# STM32F103C8T6_Schematic.net
KiCad netlist of a schematic drawn in Altium Designer
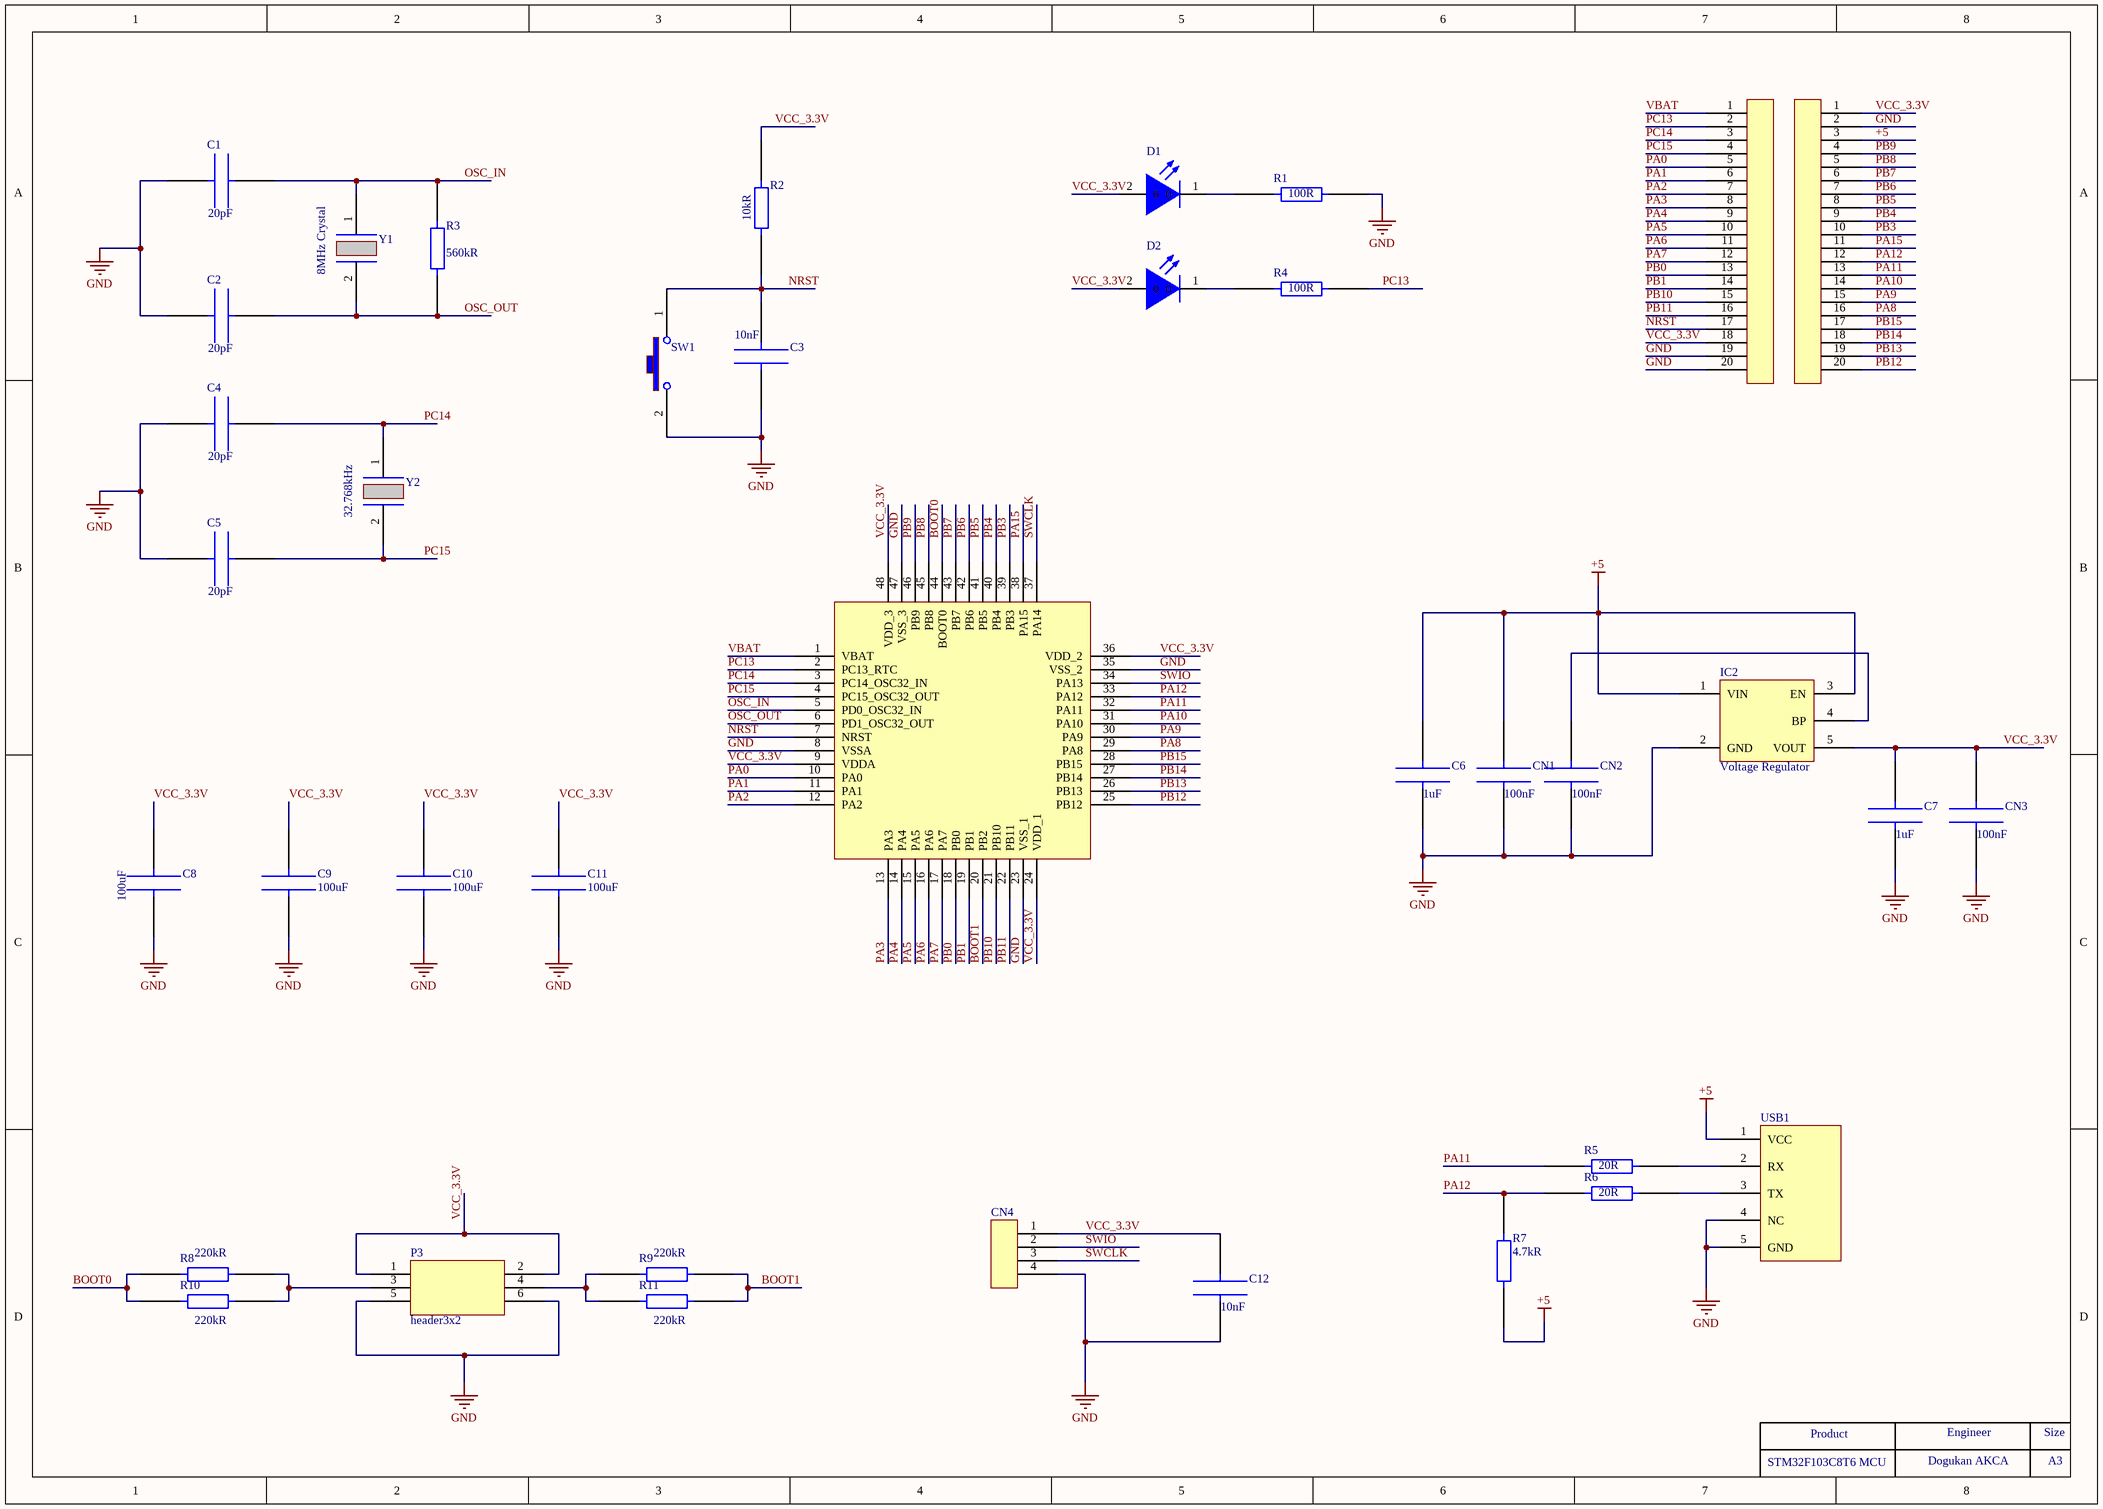
[diagram p0: STM32F103C8T6_Schematic.SchDoc]

(export (version "E")
  (design (tool "Eeschema 10.0.6"))
  (components
    (comp (ref "C1")
      (value "CAP CER 20PF 50V C0G/NP0 0603")
      (footprint "0603_CAP")
      (fields
        (field (name "MANUFACTURER") "Samsung")
        (field (name "MANUFACTURER PART NUMBER") "CL10C200JB8NNNC")
        (field (name "TOLERANCE") "5%")
        (field (name "CAPACITANCE") "20pF")
        (field (name "DESIGNER") "Dogukan")
      )
      (libsource (lib "STM32F103C8T6_Library") (part "CAP CER 20PF 50V C0G/NP0 0603"))
    )
    (comp (ref "C2")
      (value "CAP CER 20PF 50V C0G/NP0 0603")
      (footprint "0603_CAP")
      (fields
        (field (name "MANUFACTURER") "Samsung")
        (field (name "MANUFACTURER PART NUMBER") "CL10C200JB8NNNC")
        (field (name "TOLERANCE") "5%")
        (field (name "CAPACITANCE") "20pF")
        (field (name "DESIGNER") "Dogukan")
      )
      (libsource (lib "STM32F103C8T6_Library") (part "CAP CER 20PF 50V C0G/NP0 0603"))
    )
    (comp (ref "C3")
      (value "CAP CER 10nF 50V X7R 0603")
      (footprint "0603_CAP")
      (description "Cap Ceramic 0.01uF 50V X7R 5% SMD 0603 125C Paper T/R")
      (fields
        (field (name "MANUFACTURER") "Yageo")
        (field (name "MANUFACTURER PART NUMBER") "CC0603JPX7R9BB103")
        (field (name "CAPACITANCE") "10nF")
        (field (name "DESIGNER") "Dogukan")
      )
      (libsource (lib "STM32F103C8T6_Library") (part "CAP CER 10nF 50V X7R 0603"))
    )
    (comp (ref "C4")
      (value "CAP CER 20PF 50V C0G/NP0 0603")
      (footprint "0603_CAP")
      (fields
        (field (name "MANUFACTURER") "Samsung")
        (field (name "MANUFACTURER PART NUMBER") "CL10C200JB8NNNC")
        (field (name "TOLERANCE") "5%")
        (field (name "CAPACITANCE") "20pF")
        (field (name "DESIGNER") "Dogukan")
      )
      (libsource (lib "STM32F103C8T6_Library") (part "CAP CER 20PF 50V C0G/NP0 0603"))
    )
    (comp (ref "C5")
      (value "CAP CER 20PF 50V C0G/NP0 0603")
      (footprint "0603_CAP")
      (fields
        (field (name "MANUFACTURER") "Samsung")
        (field (name "MANUFACTURER PART NUMBER") "CL10C200JB8NNNC")
        (field (name "TOLERANCE") "5%")
        (field (name "CAPACITANCE") "20pF")
        (field (name "DESIGNER") "Dogukan")
      )
      (libsource (lib "STM32F103C8T6_Library") (part "CAP CER 20PF 50V C0G/NP0 0603"))
    )
    (comp (ref "C6")
      (value "CAP CER 1UF 0805")
      (footprint "CAP_0805")
      (description "CAP CER 1UF 50V X7R 0805")
      (fields
        (field (name "MANUFACTURER") "Samsung")
        (field (name "MANUFACTURER PART NUMBER") "CL21B105KBFNNNE")
        (field (name "CAPACITANCE") "1uF")
        (field (name "DESIGNER") "Dogukan")
      )
      (libsource (lib "STM32F103C8T6_Library") (part "CAP CER 1UF 0805"))
    )
    (comp (ref "C7")
      (value "CAP CER 1UF 0805")
      (footprint "CAP_0805")
      (description "CAP CER 1UF 50V X7R 0805")
      (fields
        (field (name "MANUFACTURER") "Samsung")
        (field (name "MANUFACTURER PART NUMBER") "CL21B105KBFNNNE")
        (field (name "CAPACITANCE") "1uF")
        (field (name "DESIGNER") "Dogukan")
      )
      (libsource (lib "STM32F103C8T6_Library") (part "CAP CER 1UF 0805"))
    )
    (comp (ref "C8")
      (value "CAP CER 100uf MLCC")
      (footprint "CAP_0805")
      (description "Cap 100UF 4VDC Z6S 20% SMD 0805 Embossed Tape")
      (fields
        (field (name "MANUFACTURER") "Murata")
        (field (name "MANUFACTURER PART NUMBER") "GRM21BC80G107ME15K")
        (field (name "CAPACITANCE") "100uF")
        (field (name "DESIGNER") "Dogukan")
      )
      (libsource (lib "STM32F103C8T6_Library") (part "CAP CER 100uf MLCC"))
    )
    (comp (ref "C9")
      (value "CAP CER 100uf MLCC")
      (footprint "CAP_0805")
      (description "Cap 100UF 4VDC Z6S 20% SMD 0805 Embossed Tape")
      (fields
        (field (name "MANUFACTURER") "Murata")
        (field (name "MANUFACTURER PART NUMBER") "GRM21BC80G107ME15K")
        (field (name "CAPACITANCE") "100uF")
        (field (name "DESIGNER") "Dogukan")
      )
      (libsource (lib "STM32F103C8T6_Library") (part "CAP CER 100uf MLCC"))
    )
    (comp (ref "C10")
      (value "CAP CER 100uf MLCC")
      (footprint "CAP_0805")
      (description "Cap 100UF 4VDC Z6S 20% SMD 0805 Embossed Tape")
      (fields
        (field (name "MANUFACTURER") "Murata")
        (field (name "MANUFACTURER PART NUMBER") "GRM21BC80G107ME15K")
        (field (name "CAPACITANCE") "100uF")
        (field (name "DESIGNER") "Dogukan")
      )
      (libsource (lib "STM32F103C8T6_Library") (part "CAP CER 100uf MLCC"))
    )
    (comp (ref "C11")
      (value "CAP CER 100uf MLCC")
      (footprint "CAP_0805")
      (description "Cap 100UF 4VDC Z6S 20% SMD 0805 Embossed Tape")
      (fields
        (field (name "MANUFACTURER") "Murata")
        (field (name "MANUFACTURER PART NUMBER") "GRM21BC80G107ME15K")
        (field (name "CAPACITANCE") "100uF")
        (field (name "DESIGNER") "Dogukan")
      )
      (libsource (lib "STM32F103C8T6_Library") (part "CAP CER 100uf MLCC"))
    )
    (comp (ref "C12")
      (value "CAP CER 10nF 50V X7R 0603")
      (footprint "0603_CAP")
      (description "Cap Ceramic 0.01uF 50V X7R 5% SMD 0603 125C Paper T/R")
      (fields
        (field (name "MANUFACTURER") "Yageo")
        (field (name "MANUFACTURER PART NUMBER") "CC0603JPX7R9BB103")
        (field (name "CAPACITANCE") "10nF")
        (field (name "DESIGNER") "Dogukan")
      )
      (libsource (lib "STM32F103C8T6_Library") (part "CAP CER 10nF 50V X7R 0603"))
    )
    (comp (ref "CN1")
      (value "C0603 0.1uf")
      (footprint "0603_CAP")
      (description "Multilayer Ceramic Capacitors (MLCC) - SMD/SMT 50volts 0.1uF X7R 10%")
      (fields
        (field (name "MANUFACTURER") "KEMET")
        (field (name "MANUFACTURER PART NUMBER") "C0603C104K5RACTU")
        (field (name "CAPACITANCE") "100nF")
        (field (name "DESIGNER") "Dogukan")
      )
      (libsource (lib "STM32F103C8T6_Library") (part "C0603 0.1uf"))
    )
    (comp (ref "CN2")
      (value "C0603 0.1uf")
      (footprint "0603_CAP")
      (description "Multilayer Ceramic Capacitors (MLCC) - SMD/SMT 50volts 0.1uF X7R 10%")
      (fields
        (field (name "MANUFACTURER") "KEMET")
        (field (name "MANUFACTURER PART NUMBER") "C0603C104K5RACTU")
        (field (name "CAPACITANCE") "100nF")
        (field (name "DESIGNER") "Dogukan")
      )
      (libsource (lib "STM32F103C8T6_Library") (part "C0603 0.1uf"))
    )
    (comp (ref "CN3")
      (value "C0603 0.1uf")
      (footprint "0603_CAP")
      (description "Multilayer Ceramic Capacitors (MLCC) - SMD/SMT 50volts 0.1uF X7R 10%")
      (fields
        (field (name "MANUFACTURER") "KEMET")
        (field (name "MANUFACTURER PART NUMBER") "C0603C104K5RACTU")
        (field (name "CAPACITANCE") "100nF")
        (field (name "DESIGNER") "Dogukan")
      )
      (libsource (lib "STM32F103C8T6_Library") (part "C0603 0.1uf"))
    )
    (comp (ref "CN4")
      (value "CONN HDR STRIP SOLDER 4POS GOLD")
      (footprint "4 pin konnektor pin")
      (description "Headers & Wire Housings Low Profile RT Angle Solder Cup Header")
      (fields
        (field (name "MANUFACTURER") "Mill-Max")
        (field (name "MANUFACTURER PART NUMBER") "380-10-104-10-003000")
        (field (name "DESIGNER") "Dogukan")
      )
      (libsource (lib "STM32F103C8T6_Library") (part "KONNEKTOR 4POS"))
    )
    (comp (ref "D1")
      (value "LED GREEN CLEAR CHIP SMD")
      (footprint "0805_LED_GREEN")
      (description "Green 569nm LED Indication - Discrete 2.1V 0805 (2012 Metric)")
      (fields
        (field (name "MANUFACTURER") "Vishay Lite-On")
        (field (name "MANUFACTURER PART NUMBER") "LTST-C171GKT")
        (field (name "DESIGNER") "Dogukan")
      )
      (libsource (lib "STM32F103C8T6_Library") (part "LED GREEN CLEAR CHIP SMD"))
    )
    (comp (ref "D2")
      (value "LED GREEN CLEAR CHIP SMD")
      (footprint "0805_LED_GREEN")
      (description "Green 569nm LED Indication - Discrete 2.1V 0805 (2012 Metric)")
      (fields
        (field (name "MANUFACTURER") "Vishay Lite-On")
        (field (name "MANUFACTURER PART NUMBER") "LTST-C171GKT")
        (field (name "DESIGNER") "Dogukan")
      )
      (libsource (lib "STM32F103C8T6_Library") (part "LED GREEN CLEAR CHIP SMD"))
    )
    (comp (ref "IC1")
      (value "IC MCU 32BIT 64KB FLASH 48LQFP")
      (footprint "LQFP48")
      (description "ARM Cortex-M3 STM32 F1 Microcontroller 32-Bit 72MHz 64kB FLASH LQFP48 STM32F103C8T6")
      (fields
        (field (name "MANUFACTURER") "STMicroelectronics")
        (field (name "MANUFACTURER PART NUMBER") "STM32F103C8T6")
        (field (name "DESIGNER") "Dogukan")
      )
      (libsource (lib "STM32F103C8T6_Library") (part "STM32F103C8T6"))
    )
    (comp (ref "IC2")
      (value "IC REG LINEAR 3.3V 300MA SOT23-5")
      (footprint "SOT23-5")
      (description "IC REG LDO 3.3V 0.3A SOT23-5")
      (fields
        (field (name "MANUFACTURER") "Richtek")
        (field (name "MANUFACTURER PART NUMBER") "RT9193-33GB")
        (field (name "CATEGORY") "Voltage Regulator")
        (field (name "DESIGNER") "Dogukan")
      )
      (libsource (lib "STM32F103C8T6_Library") (part "Voltage Regulator_5V-{gt}3.3V"))
    )
    (comp (ref "P1")
      (value "CONN SIL HDR MALE PIN 20POS TIN")
      (footprint "20pin1x20_header_connector")
      (description "2.54mm (0.1\") Pitch SIL Vertical Through Connect Header Strip, tin (hi-temp mould), 20 contacts")
      (fields
        (field (name "MANUFACTURER") "Harwin")
        (field (name "MANUFACTURER PART NUMBER") "D01-9922046")
        (field (name "DESIGNER") "Dogukan")
      )
      (libsource (lib "") (part "header_20pin_1"))
    )
    (comp (ref "P2")
      (value "CONN SIL HDR MALE PIN 20POS TIN")
      (footprint "20pin1x20_header_connector")
      (description "2.54mm (0.1\") Pitch SIL Vertical Through Connect Header Strip, tin (hi-temp mould), 20 contacts")
      (fields
        (field (name "MANUFACTURER") "Harwin")
        (field (name "MANUFACTURER PART NUMBER") "D01-9922046")
        (field (name "DESIGNER") "Dogukan")
      )
      (libsource (lib "STM32F103C8T6_Library") (part "header_20pin"))
    )
    (comp (ref "P3")
      (value "header3x2")
      (footprint "header3x2")
      (fields (field (name "DESIGNER") "Dogukan"))
      (libsource (lib "STM32F103C8T6_Library") (part "header3x2"))
    )
    (comp (ref "R1")
      (value "100R")
      (footprint "0603_RES")
      (description "Res Thick Film 0603 100 Ohm 1% 1/10W ±100ppm/°C Molded SMD Paper T/R")
      (fields
        (field (name "MANUFACTURER") "Yageo")
        (field (name "MANUFACTURER PART NUMBER") "RC0603FR-07100RL")
        (field (name "DESIGNER") "Dogukan")
      )
      (libsource (lib "STM32F103C8T6_Library") (part "RES_100R_0603"))
    )
    (comp (ref "R2")
      (value "RES 10K OHM 0.5% 1/10W 0603")
      (footprint "0603_RES")
      (description "Res Thin Film 0603 10K Ohm 0.5% 1/10W ±25ppm/°C Molded SMD Paper T/R")
      (fields
        (field (name "MANUFACTURER") "Yageo")
        (field (name "MANUFACTURER PART NUMBER") "RT0603DRD0710KL")
        (field (name "RESISTANCE") "10kR")
        (field (name "DESIGNER") "Dogukan")
      )
      (libsource (lib "STM32F103C8T6_Library") (part "RES 10K OHM 0.5% 1/10W 0603"))
    )
    (comp (ref "R3")
      (value "RES 560K OHM 5% 1/10W 0603")
      (footprint "0603_RES")
      (description "Res Thick Film 0603 560K Ohm 5% 0.1W(1/10W) ±100ppm/C Molded SMD Paper T/R")
      (fields
        (field (name "MANUFACTURER") "Yageo")
        (field (name "MANUFACTURER PART NUMBER") "RC0603JR-07560KL")
        (field (name "RESISTANCE") "560kR")
        (field (name "DESIGNER") "Dogukan")
      )
      (libsource (lib "STM32F103C8T6_Library") (part "RES 560K OHM 5% 1/10W 0603"))
    )
    (comp (ref "R4")
      (value "100R")
      (footprint "0603_RES")
      (description "Res Thick Film 0603 100 Ohm 1% 1/10W ±100ppm/°C Molded SMD Paper T/R")
      (fields
        (field (name "MANUFACTURER") "Yageo")
        (field (name "MANUFACTURER PART NUMBER") "RC0603FR-07100RL")
        (field (name "DESIGNER") "Dogukan")
      )
      (libsource (lib "STM32F103C8T6_Library") (part "RES_100R_0603"))
    )
    (comp (ref "R5")
      (value "*RES 20 OHM 5% 1/10W 0603")
      (footprint "0603_RES")
      (description "Res Thick Film 0603 20 Ohm 5% 1/10W +/-100ppm/ßC Molded SMD Paper T/R")
      (fields
        (field (name "MANUFACTURER") "Yageo")
        (field (name "MANUFACTURER PART NUMBER") "RC0603JR-0720RL")
        (field (name "R") "20R")
        (field (name "DESIGNER") "Dogukan")
      )
      (libsource (lib "STM32F103C8T6_Library") (part "RES 20 OHM 5% 1/10W 0603"))
    )
    (comp (ref "R6")
      (value "*RES 20 OHM 5% 1/10W 0603")
      (footprint "0603_RES")
      (description "Res Thick Film 0603 20 Ohm 5% 1/10W +/-100ppm/ßC Molded SMD Paper T/R")
      (fields
        (field (name "MANUFACTURER") "Yageo")
        (field (name "MANUFACTURER PART NUMBER") "RC0603JR-0720RL")
        (field (name "R") "20R")
        (field (name "DESIGNER") "Dogukan")
      )
      (libsource (lib "STM32F103C8T6_Library") (part "RES 20 OHM 5% 1/10W 0603"))
    )
    (comp (ref "R7")
      (value "RES 4.7K OHM 5% 1/10W 0603")
      (footprint "0603_RES")
      (description "Res General Purpose Thick Film 0603 4.7k Ohm 5% 1/10W ±100ppm/°C Molded Paper T/R")
      (fields
        (field (name "MANUFACTURER") "Yageo")
        (field (name "MANUFACTURER PART NUMBER") "RC0603JR-074K7L")
        (field (name "RESISTANCE") "4.7kR")
        (field (name "DESIGNER") "Dogukan")
      )
      (libsource (lib "STM32F103C8T6_Library") (part "RES 4.7K OHM 5% 1/10W 0603"))
    )
    (comp (ref "R8")
      (value "RES 220K OHM 5% 1/10W 0603")
      (footprint "0603_RES")
      (description "Res Thick Film 0603 220K Ohm 5% 0.1W(1/10W) ±100ppm/C Pad SMD T/R")
      (fields
        (field (name "MANUFACTURER") "Yageo")
        (field (name "MANUFACTURER PART NUMBER") "RC0603JR-07220KL")
        (field (name "RESISTANCE") "220kR")
        (field (name "DESIGNER") "Dogukan")
      )
      (libsource (lib "STM32F103C8T6_Library") (part "RES 220K OHM 5% 1/10W 0603"))
    )
    (comp (ref "R9")
      (value "RES 220K OHM 5% 1/10W 0603")
      (footprint "0603_RES")
      (description "Res Thick Film 0603 220K Ohm 5% 0.1W(1/10W) ±100ppm/C Pad SMD T/R")
      (fields
        (field (name "MANUFACTURER") "Yageo")
        (field (name "MANUFACTURER PART NUMBER") "RC0603JR-07220KL")
        (field (name "RESISTANCE") "220kR")
        (field (name "DESIGNER") "Dogukan")
      )
      (libsource (lib "STM32F103C8T6_Library") (part "RES 220K OHM 5% 1/10W 0603"))
    )
    (comp (ref "R10")
      (value "RES 220K OHM 5% 1/10W 0603")
      (footprint "0603_RES")
      (description "Res Thick Film 0603 220K Ohm 5% 0.1W(1/10W) ±100ppm/C Pad SMD T/R")
      (fields
        (field (name "MANUFACTURER") "Yageo")
        (field (name "MANUFACTURER PART NUMBER") "RC0603JR-07220KL")
        (field (name "RESISTANCE") "220kR")
        (field (name "DESIGNER") "Dogukan")
      )
      (libsource (lib "STM32F103C8T6_Library") (part "RES 220K OHM 5% 1/10W 0603"))
    )
    (comp (ref "R11")
      (value "RES 220K OHM 5% 1/10W 0603")
      (footprint "0603_RES")
      (description "Res Thick Film 0603 220K Ohm 5% 0.1W(1/10W) ±100ppm/C Pad SMD T/R")
      (fields
        (field (name "MANUFACTURER") "Yageo")
        (field (name "MANUFACTURER PART NUMBER") "RC0603JR-07220KL")
        (field (name "RESISTANCE") "220kR")
        (field (name "DESIGNER") "Dogukan")
      )
      (libsource (lib "STM32F103C8T6_Library") (part "RES 220K OHM 5% 1/10W 0603"))
    )
    (comp (ref "SW1")
      (value "push button switch")
      (footprint "push_button")
      (libsource (lib "STM32F103C8T6_Library") (part "push_button"))
    )
    (comp (ref "USB1")
      (value "CONN RCPT USB2.0 MICRO B SMD R/A")
      (footprint "MICRO B USB2.0 SMD R/A")
      (description "CONN USB MICRO B RECPT SMT R/A")
      (fields
        (field (name "MANUFACTURER") "Amphenol ICC / FCI")
        (field (name "MANUFACTURER PART NUMBER") "10118192-0001LF")
        (field (name "DESIGNER") "Dogukan")
      )
      (libsource (lib "STM32F103C8T6_Library") (part "CONN RCPT USB2.0 MICRO B SMD R/A"))
    )
    (comp (ref "Y1")
      (value "CRYSTAL 8.0000MHZ 18PF SMD")
      (footprint "USX SMD T_8MHz Crystal")
      (description "Crystal 8MHz ±30ppm (Tol) ±50ppm (Stability) 18pF FUND 60Ohm 2-Pin HC-49/USX SMD T/R")
      (fields
        (field (name "MANUFACTURER") "ECS International")
        (field (name "MANUFACTURER PART NUMBER") "ECS-80-18-5PX-TR")
        (field (name "CATEGORY") "8MHz Crystal")
        (field (name "DESIGNER") "Dogukan")
      )
      (libsource (lib "STM32F103C8T6_Library") (part "CRYSTAL 8.0000MHZ 18PF SMD"))
    )
    (comp (ref "Y2")
      (value "CRYSTAL 32.7680KHZ 12.5PF SMD")
      (footprint "2-SMD_CRYSTAL 32.7680KHZ")
      (description "Crystal 0.032768MHz ±20ppm (Tol) 12.5pF Flexural 90000Ohm 2-Pin CSMD T/R")
      (fields
        (field (name "MANUFACTURER") "Abracon")
        (field (name "MANUFACTURER PART NUMBER") "ABS05-32.768KHZ-T")
        (field (name "FREQUENCY") "32.768kHz")
        (field (name "DESIGNER") "Dogukan")
      )
      (libsource (lib "STM32F103C8T6_Library") (part "CRYSTAL 32.7680KHZ 12.5PF SMD"))
    )
  )
  (nets
    (net (code "1") (name "+5") (class "Default")
      (node (ref "C6") (pin "2") (pinfunction "27_2") (pintype "passive"))
      (node (ref "CN1") (pin "2") (pinfunction "27_2") (pintype "passive"))
      (node (ref "IC2") (pin "1") (pinfunction "VIN_1") (pintype "passive"))
      (node (ref "IC2") (pin "3") (pinfunction "EN_3") (pintype "passive"))
      (node (ref "P2") (pin "3") (pinfunction "3_3") (pintype "passive"))
      (node (ref "R7") (pin "1") (pinfunction "25_1") (pintype "passive"))
      (node (ref "USB1") (pin "1") (pinfunction "VCC_1") (pintype "passive"))
    )
    (net (code "2") (name "/BOOT0") (class "Default")
      (node (ref "IC1") (pin "44") (pinfunction "BOOT0_44") (pintype "passive"))
      (node (ref "R10") (pin "1") (pinfunction "25_1") (pintype "passive"))
      (node (ref "R8") (pin "1") (pinfunction "25_1") (pintype "passive"))
    )
    (net (code "3") (name "/BOOT1") (class "Default")
      (node (ref "IC1") (pin "20") (pinfunction "PB2_20") (pintype "passive"))
      (node (ref "R11") (pin "2") (pinfunction "24_2") (pintype "passive"))
      (node (ref "R9") (pin "2") (pinfunction "24_2") (pintype "passive"))
    )
    (net (code "4") (name "/NRST") (class "Default")
      (node (ref "C3") (pin "2") (pinfunction "27_2") (pintype "passive"))
      (node (ref "IC1") (pin "7") (pinfunction "NRST_7") (pintype "passive"))
      (node (ref "P1") (pin "17") (pinfunction "17_17") (pintype "passive"))
      (node (ref "R2") (pin "1") (pinfunction "25_1") (pintype "passive"))
      (node (ref "SW1") (pin "1") (pinfunction "1_1") (pintype "passive"))
    )
    (net (code "5") (name "/OSC_IN") (class "Default")
      (node (ref "C1") (pin "2") (pinfunction "27_2") (pintype "passive"))
      (node (ref "IC1") (pin "5") (pinfunction "PD0_OSC32_IN_5") (pintype "passive"))
      (node (ref "R3") (pin "2") (pinfunction "24_2") (pintype "passive"))
      (node (ref "Y1") (pin "1") (pinfunction "4_1") (pintype "passive"))
    )
    (net (code "6") (name "/OSC_OUT") (class "Default")
      (node (ref "C2") (pin "2") (pinfunction "27_2") (pintype "passive"))
      (node (ref "IC1") (pin "6") (pinfunction "PD1_OSC32_OUT_6") (pintype "passive"))
      (node (ref "R3") (pin "1") (pinfunction "25_1") (pintype "passive"))
      (node (ref "Y1") (pin "2") (pinfunction "5_2") (pintype "passive"))
    )
    (net (code "7") (name "/PA0") (class "Default")
      (node (ref "IC1") (pin "10") (pinfunction "PA0_10") (pintype "passive"))
      (node (ref "P1") (pin "5") (pinfunction "5_5") (pintype "passive"))
    )
    (net (code "8") (name "/PA1") (class "Default")
      (node (ref "IC1") (pin "11") (pinfunction "PA1_11") (pintype "passive"))
      (node (ref "P1") (pin "6") (pinfunction "6_6") (pintype "passive"))
    )
    (net (code "9") (name "/PA2") (class "Default")
      (node (ref "IC1") (pin "12") (pinfunction "PA2_12") (pintype "passive"))
      (node (ref "P1") (pin "7") (pinfunction "7_7") (pintype "passive"))
    )
    (net (code "10") (name "/PA3") (class "Default")
      (node (ref "IC1") (pin "13") (pinfunction "PA3_13") (pintype "passive"))
      (node (ref "P1") (pin "8") (pinfunction "8_8") (pintype "passive"))
    )
    (net (code "11") (name "/PA4") (class "Default")
      (node (ref "IC1") (pin "14") (pinfunction "PA4_14") (pintype "passive"))
      (node (ref "P1") (pin "9") (pinfunction "9_9") (pintype "passive"))
    )
    (net (code "12") (name "/PA5") (class "Default")
      (node (ref "IC1") (pin "15") (pinfunction "PA5_15") (pintype "passive"))
      (node (ref "P1") (pin "10") (pinfunction "10_10") (pintype "passive"))
    )
    (net (code "13") (name "/PA6") (class "Default")
      (node (ref "IC1") (pin "16") (pinfunction "PA6_16") (pintype "passive"))
      (node (ref "P1") (pin "11") (pinfunction "11_11") (pintype "passive"))
    )
    (net (code "14") (name "/PA7") (class "Default")
      (node (ref "IC1") (pin "17") (pinfunction "PA7_17") (pintype "passive"))
      (node (ref "P1") (pin "12") (pinfunction "12_12") (pintype "passive"))
    )
    (net (code "15") (name "/PA8") (class "Default")
      (node (ref "IC1") (pin "29") (pinfunction "PA8_29") (pintype "passive"))
      (node (ref "P2") (pin "16") (pinfunction "16_16") (pintype "passive"))
    )
    (net (code "16") (name "/PA9") (class "Default")
      (node (ref "IC1") (pin "30") (pinfunction "PA9_30") (pintype "passive"))
      (node (ref "P2") (pin "15") (pinfunction "15_15") (pintype "passive"))
    )
    (net (code "17") (name "/PA10") (class "Default")
      (node (ref "IC1") (pin "31") (pinfunction "PA10_31") (pintype "passive"))
      (node (ref "P2") (pin "14") (pinfunction "14_14") (pintype "passive"))
    )
    (net (code "18") (name "/PA11") (class "Default")
      (node (ref "IC1") (pin "32") (pinfunction "PA11_32") (pintype "passive"))
      (node (ref "P2") (pin "13") (pinfunction "13_13") (pintype "passive"))
      (node (ref "R5") (pin "1") (pinfunction "25_1") (pintype "passive"))
    )
    (net (code "19") (name "/PA12") (class "Default")
      (node (ref "IC1") (pin "33") (pinfunction "PA12_33") (pintype "passive"))
      (node (ref "P2") (pin "12") (pinfunction "12_12") (pintype "passive"))
      (node (ref "R6") (pin "1") (pinfunction "25_1") (pintype "passive"))
      (node (ref "R7") (pin "2") (pinfunction "24_2") (pintype "passive"))
    )
    (net (code "20") (name "/PA15") (class "Default")
      (node (ref "IC1") (pin "38") (pinfunction "PA15_38") (pintype "passive"))
      (node (ref "P2") (pin "11") (pinfunction "11_11") (pintype "passive"))
    )
    (net (code "21") (name "/PB0") (class "Default")
      (node (ref "IC1") (pin "18") (pinfunction "PB0_18") (pintype "passive"))
      (node (ref "P1") (pin "13") (pinfunction "13_13") (pintype "passive"))
    )
    (net (code "22") (name "/PB1") (class "Default")
      (node (ref "IC1") (pin "19") (pinfunction "PB1_19") (pintype "passive"))
      (node (ref "P1") (pin "14") (pinfunction "14_14") (pintype "passive"))
    )
    (net (code "23") (name "/PB3") (class "Default")
      (node (ref "IC1") (pin "39") (pinfunction "PB3_39") (pintype "passive"))
      (node (ref "P2") (pin "10") (pinfunction "10_10") (pintype "passive"))
    )
    (net (code "24") (name "/PB4") (class "Default")
      (node (ref "IC1") (pin "40") (pinfunction "PB4_40") (pintype "passive"))
      (node (ref "P2") (pin "9") (pinfunction "9_9") (pintype "passive"))
    )
    (net (code "25") (name "/PB5") (class "Default")
      (node (ref "IC1") (pin "41") (pinfunction "PB5_41") (pintype "passive"))
      (node (ref "P2") (pin "8") (pinfunction "8_8") (pintype "passive"))
    )
    (net (code "26") (name "/PB6") (class "Default")
      (node (ref "IC1") (pin "42") (pinfunction "PB6_42") (pintype "passive"))
      (node (ref "P2") (pin "7") (pinfunction "7_7") (pintype "passive"))
    )
    (net (code "27") (name "/PB7") (class "Default")
      (node (ref "IC1") (pin "43") (pinfunction "PB7_43") (pintype "passive"))
      (node (ref "P2") (pin "6") (pinfunction "6_6") (pintype "passive"))
    )
    (net (code "28") (name "/PB8") (class "Default")
      (node (ref "IC1") (pin "45") (pinfunction "PB8_45") (pintype "passive"))
      (node (ref "P2") (pin "5") (pinfunction "5_5") (pintype "passive"))
    )
    (net (code "29") (name "/PB9") (class "Default")
      (node (ref "IC1") (pin "46") (pinfunction "PB9_46") (pintype "passive"))
      (node (ref "P2") (pin "4") (pinfunction "4_4") (pintype "passive"))
    )
    (net (code "30") (name "/PB10") (class "Default")
      (node (ref "IC1") (pin "21") (pinfunction "PB10_21") (pintype "passive"))
      (node (ref "P1") (pin "15") (pinfunction "15_15") (pintype "passive"))
    )
    (net (code "31") (name "/PB11") (class "Default")
      (node (ref "IC1") (pin "22") (pinfunction "PB11_22") (pintype "passive"))
      (node (ref "P1") (pin "16") (pinfunction "16_16") (pintype "passive"))
    )
    (net (code "32") (name "/PB12") (class "Default")
      (node (ref "IC1") (pin "25") (pinfunction "PB12_25") (pintype "passive"))
      (node (ref "P2") (pin "20") (pinfunction "20_20") (pintype "passive"))
    )
    (net (code "33") (name "/PB13") (class "Default")
      (node (ref "IC1") (pin "26") (pinfunction "PB13_26") (pintype "passive"))
      (node (ref "P2") (pin "19") (pinfunction "19_19") (pintype "passive"))
    )
    (net (code "34") (name "/PB14") (class "Default")
      (node (ref "IC1") (pin "27") (pinfunction "PB14_27") (pintype "passive"))
      (node (ref "P2") (pin "18") (pinfunction "18_18") (pintype "passive"))
    )
    (net (code "35") (name "/PB15") (class "Default")
      (node (ref "IC1") (pin "28") (pinfunction "PB15_28") (pintype "passive"))
      (node (ref "P2") (pin "17") (pinfunction "17_17") (pintype "passive"))
    )
    (net (code "36") (name "/PC13") (class "Default")
      (node (ref "IC1") (pin "2") (pinfunction "PC13_RTC_2") (pintype "passive"))
      (node (ref "P1") (pin "2") (pinfunction "2_2") (pintype "passive"))
      (node (ref "R4") (pin "2") (pinfunction "24_2") (pintype "passive"))
    )
    (net (code "37") (name "/PC14") (class "Default")
      (node (ref "C4") (pin "2") (pinfunction "27_2") (pintype "passive"))
      (node (ref "IC1") (pin "3") (pinfunction "PC14_OSC32_IN_3") (pintype "passive"))
      (node (ref "P1") (pin "3") (pinfunction "3_3") (pintype "passive"))
      (node (ref "Y2") (pin "1") (pinfunction "4_1") (pintype "passive"))
    )
    (net (code "38") (name "/PC15") (class "Default")
      (node (ref "C5") (pin "2") (pinfunction "27_2") (pintype "passive"))
      (node (ref "IC1") (pin "4") (pinfunction "PC15_OSC32_OUT_4") (pintype "passive"))
      (node (ref "P1") (pin "4") (pinfunction "4_4") (pintype "passive"))
      (node (ref "Y2") (pin "2") (pinfunction "5_2") (pintype "passive"))
    )
    (net (code "39") (name "/SWCLK") (class "Default")
      (node (ref "CN4") (pin "3") (pinfunction "3_3") (pintype "passive"))
      (node (ref "IC1") (pin "37") (pinfunction "PA14_37") (pintype "passive"))
    )
    (net (code "40") (name "/SWIO") (class "Default")
      (node (ref "CN4") (pin "2") (pinfunction "2_2") (pintype "passive"))
      (node (ref "IC1") (pin "34") (pinfunction "PA13_34") (pintype "passive"))
    )
    (net (code "41") (name "/VBAT") (class "Default")
      (node (ref "IC1") (pin "1") (pinfunction "VBAT_1") (pintype "passive"))
      (node (ref "P1") (pin "1") (pinfunction "1_1") (pintype "passive"))
    )
    (net (code "42") (name "/VCC_3.3V") (class "Default")
      (node (ref "C10") (pin "2") (pinfunction "27_2") (pintype "passive"))
      (node (ref "C11") (pin "2") (pinfunction "27_2") (pintype "passive"))
      (node (ref "C12") (pin "2") (pinfunction "27_2") (pintype "passive"))
      (node (ref "C7") (pin "2") (pinfunction "27_2") (pintype "passive"))
      (node (ref "C8") (pin "2") (pinfunction "27_2") (pintype "passive"))
      (node (ref "C9") (pin "2") (pinfunction "27_2") (pintype "passive"))
      (node (ref "CN3") (pin "2") (pinfunction "27_2") (pintype "passive"))
      (node (ref "CN4") (pin "1") (pinfunction "1_1") (pintype "passive"))
      (node (ref "D1") (pin "2") (pinfunction "0_2") (pintype "passive"))
      (node (ref "D2") (pin "2") (pinfunction "0_2") (pintype "passive"))
      (node (ref "IC1") (pin "24") (pinfunction "VDD_1_24") (pintype "passive"))
      (node (ref "IC1") (pin "36") (pinfunction "VDD_2_36") (pintype "passive"))
      (node (ref "IC1") (pin "48") (pinfunction "VDD_3_48") (pintype "passive"))
      (node (ref "IC1") (pin "9") (pinfunction "VDDA_9") (pintype "passive"))
      (node (ref "IC2") (pin "5") (pinfunction "VOUT_5") (pintype "passive"))
      (node (ref "P1") (pin "18") (pinfunction "18_18") (pintype "passive"))
      (node (ref "P2") (pin "1") (pinfunction "1_1") (pintype "passive"))
      (node (ref "P3") (pin "1") (pinfunction "1_1") (pintype "passive"))
      (node (ref "P3") (pin "2") (pinfunction "2_2") (pintype "passive"))
      (node (ref "R2") (pin "2") (pinfunction "24_2") (pintype "passive"))
    )
    (net (code "43") (name "GND") (class "Default")
      (node (ref "C1") (pin "1") (pinfunction "26_1") (pintype "passive"))
      (node (ref "C10") (pin "1") (pinfunction "26_1") (pintype "passive"))
      (node (ref "C11") (pin "1") (pinfunction "26_1") (pintype "passive"))
      (node (ref "C12") (pin "1") (pinfunction "26_1") (pintype "passive"))
      (node (ref "C2") (pin "1") (pinfunction "26_1") (pintype "passive"))
      (node (ref "C3") (pin "1") (pinfunction "26_1") (pintype "passive"))
      (node (ref "C4") (pin "1") (pinfunction "26_1") (pintype "passive"))
      (node (ref "C5") (pin "1") (pinfunction "26_1") (pintype "passive"))
      (node (ref "C6") (pin "1") (pinfunction "26_1") (pintype "passive"))
      (node (ref "C7") (pin "1") (pinfunction "26_1") (pintype "passive"))
      (node (ref "C8") (pin "1") (pinfunction "26_1") (pintype "passive"))
      (node (ref "C9") (pin "1") (pinfunction "26_1") (pintype "passive"))
      (node (ref "CN1") (pin "1") (pinfunction "26_1") (pintype "passive"))
      (node (ref "CN2") (pin "1") (pinfunction "26_1") (pintype "passive"))
      (node (ref "CN3") (pin "1") (pinfunction "26_1") (pintype "passive"))
      (node (ref "CN4") (pin "4") (pinfunction "4_4") (pintype "passive"))
      (node (ref "IC1") (pin "23") (pinfunction "VSS_1_23") (pintype "passive"))
      (node (ref "IC1") (pin "35") (pinfunction "VSS_2_35") (pintype "passive"))
      (node (ref "IC1") (pin "47") (pinfunction "VSS_3_47") (pintype "passive"))
      (node (ref "IC1") (pin "8") (pinfunction "VSSA_8") (pintype "passive"))
      (node (ref "IC2") (pin "2") (pinfunction "GND_2") (pintype "passive"))
      (node (ref "P1") (pin "19") (pinfunction "19_19") (pintype "passive"))
      (node (ref "P1") (pin "20") (pinfunction "20_20") (pintype "passive"))
      (node (ref "P2") (pin "2") (pinfunction "2_2") (pintype "passive"))
      (node (ref "P3") (pin "5") (pinfunction "5_5") (pintype "passive"))
      (node (ref "P3") (pin "6") (pinfunction "6_6") (pintype "passive"))
      (node (ref "R1") (pin "2") (pinfunction "24_2") (pintype "passive"))
      (node (ref "SW1") (pin "2") (pinfunction "2_2") (pintype "passive"))
      (node (ref "USB1") (pin "4") (pinfunction "NC_4") (pintype "passive"))
      (node (ref "USB1") (pin "5") (pinfunction "GND_5") (pintype "passive"))
    )
    (net (code "44") (name "Net-(CN2-27)") (class "Default")
      (node (ref "CN2") (pin "2") (pinfunction "27_2") (pintype "passive"))
      (node (ref "IC2") (pin "4") (pinfunction "BP_4") (pintype "passive"))
    )
    (net (code "45") (name "Net-(R1-25)") (class "Default")
      (node (ref "D1") (pin "1") (pinfunction "0_1") (pintype "passive"))
      (node (ref "R1") (pin "1") (pinfunction "25_1") (pintype "passive"))
    )
    (net (code "46") (name "Net-(R4-25)") (class "Default")
      (node (ref "D2") (pin "1") (pinfunction "0_1") (pintype "passive"))
      (node (ref "R4") (pin "1") (pinfunction "25_1") (pintype "passive"))
    )
    (net (code "47") (name "Net-(R5-24)") (class "Default")
      (node (ref "R5") (pin "2") (pinfunction "24_2") (pintype "passive"))
      (node (ref "USB1") (pin "2") (pinfunction "RX_2") (pintype "passive"))
    )
    (net (code "48") (name "Net-(R6-24)") (class "Default")
      (node (ref "R6") (pin "2") (pinfunction "24_2") (pintype "passive"))
      (node (ref "USB1") (pin "3") (pinfunction "TX_3") (pintype "passive"))
    )
    (net (code "49") (name "Net-(R10-24)") (class "Default")
      (node (ref "P3") (pin "3") (pinfunction "3_3") (pintype "passive"))
      (node (ref "R10") (pin "2") (pinfunction "24_2") (pintype "passive"))
      (node (ref "R8") (pin "2") (pinfunction "24_2") (pintype "passive"))
    )
    (net (code "50") (name "Net-(R11-25)") (class "Default")
      (node (ref "P3") (pin "4") (pinfunction "4_4") (pintype "passive"))
      (node (ref "R11") (pin "1") (pinfunction "25_1") (pintype "passive"))
      (node (ref "R9") (pin "1") (pinfunction "25_1") (pintype "passive"))
    )
  )
)
